# BATT_CPU_TEST_BED.net
KiCad netlist of a schematic drawn in EAGLE
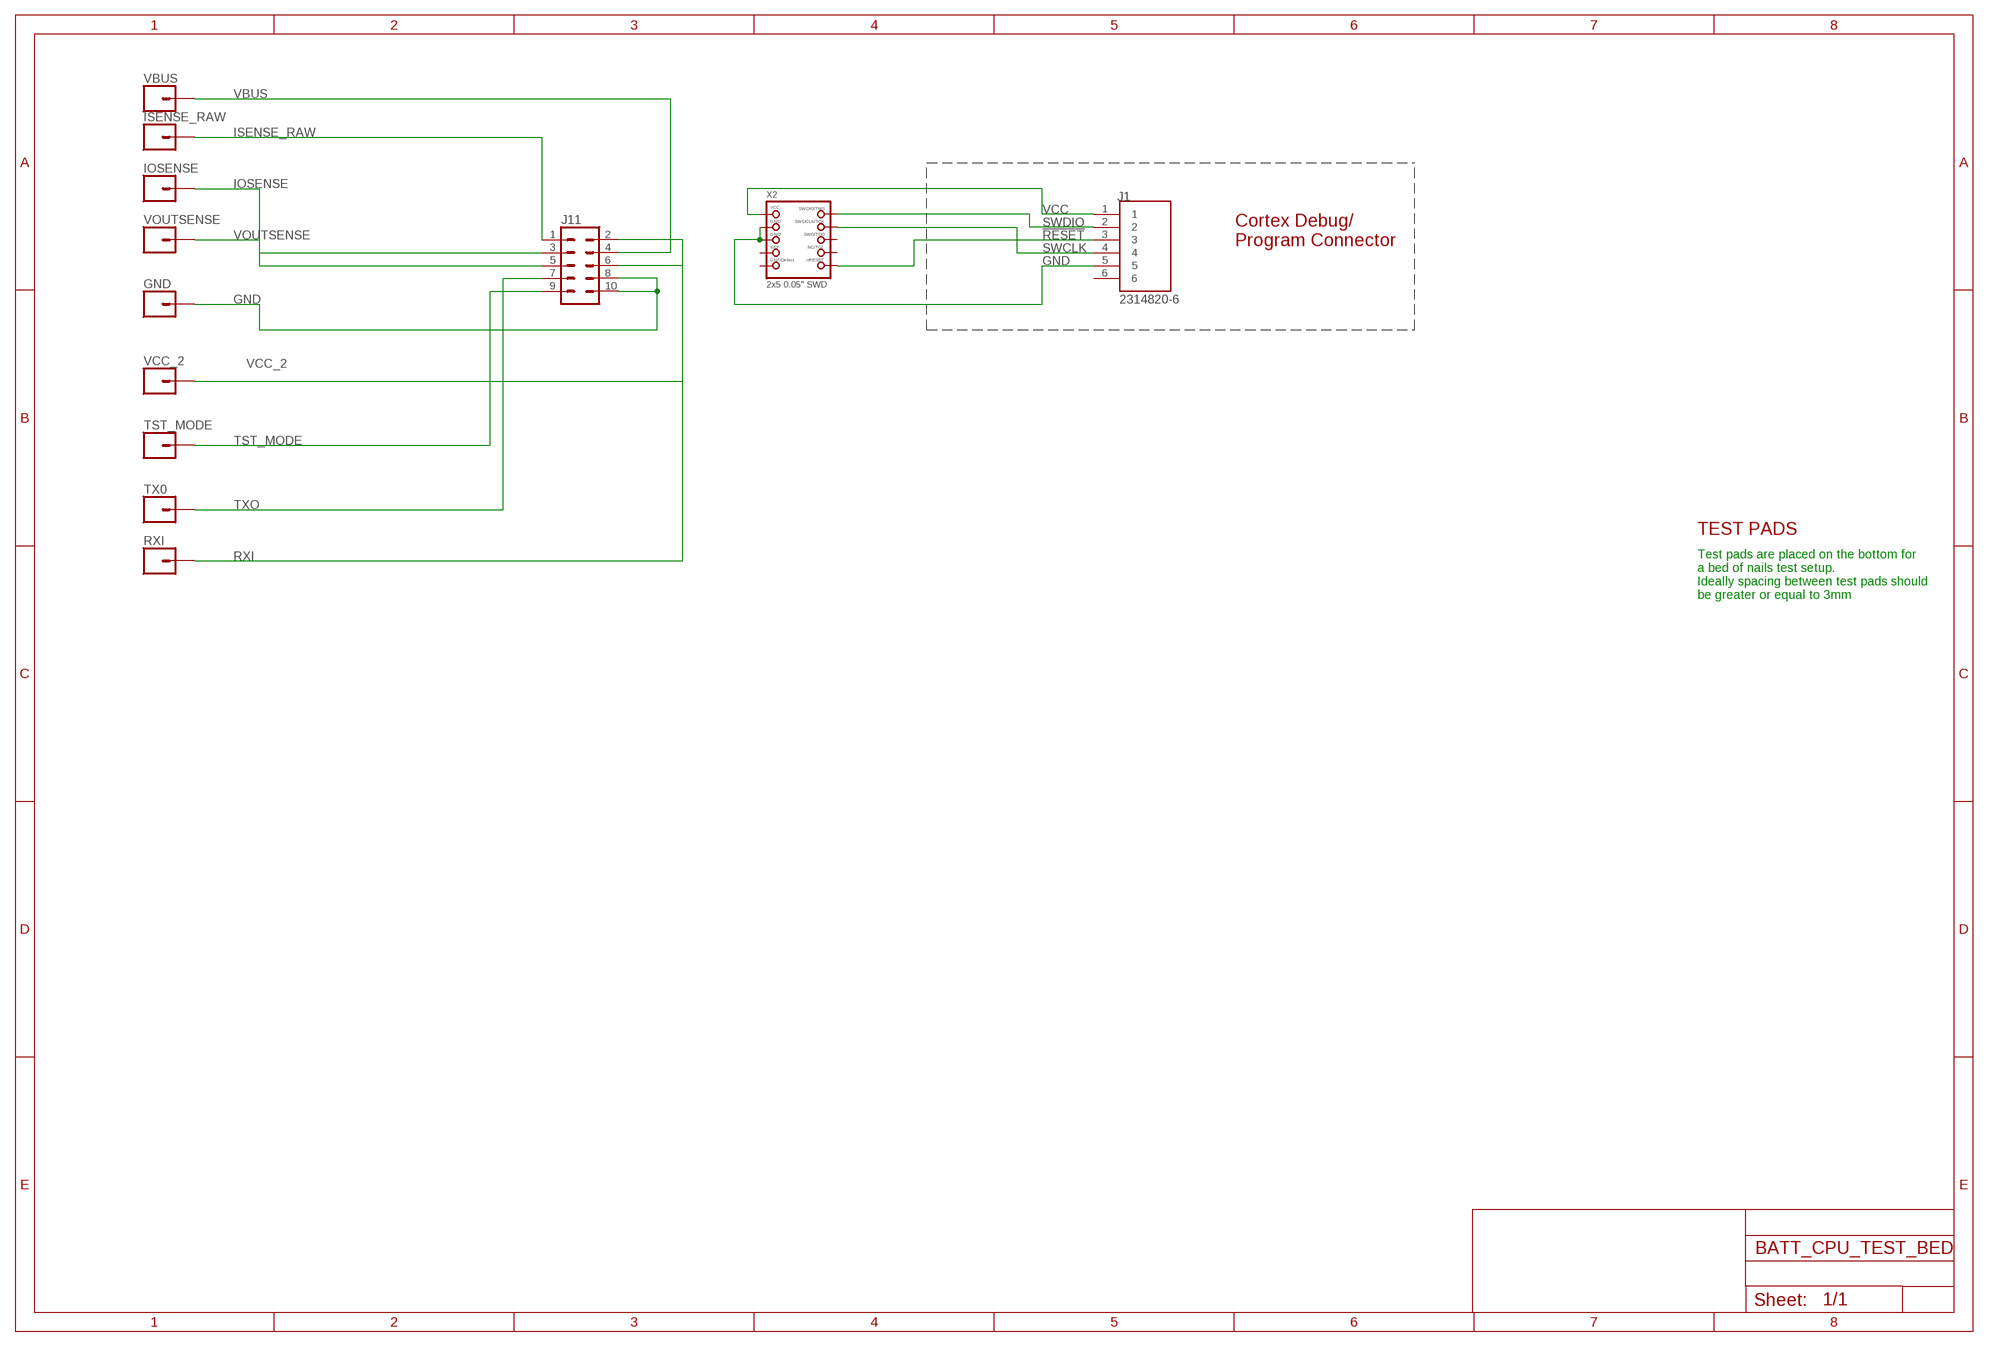
[diagram p0: schematic, sheet 1]

(export (version "E")
  (design (tool "Eeschema 10.0.6"))
  (components
    (comp (ref "GND")
      (value "CONN_01POGOPIN_HOLE_LARGE")
      (footprint "eagle-import:1X01_POGOPIN_HOLE_0.061_DIA")
      (libsource (lib "eagle-import") (part "CONN_01POGOPIN_HOLE_LARGE"))
    )
    (comp (ref "IOSENSE")
      (value "CONN_01POGOPIN_HOLE_LARGE")
      (footprint "eagle-import:1X01_POGOPIN_HOLE_0.061_DIA")
      (libsource (lib "eagle-import") (part "CONN_01POGOPIN_HOLE_LARGE"))
    )
    (comp (ref "ISENSE_RAW")
      (value "CONN_01POGOPIN_HOLE_LARGE")
      (footprint "eagle-import:1X01_POGOPIN_HOLE_0.061_DIA")
      (libsource (lib "eagle-import") (part "CONN_01POGOPIN_HOLE_LARGE"))
    )
    (comp (ref "J1")
      (value "2314820-6")
      (footprint "eagle-import:TE_2314820-6")
      (fields (field (name "DIGI-KEY_PART_NUMBER") "17-2314820-6-ND") (field (name "MF") "TE Connectivity"))
      (libsource (lib "eagle-import") (part "2314820-6"))
    )
    (comp (ref "J11")
      (value "CONN_05X2PTH")
      (footprint "eagle-import:2X5")
      (libsource (lib "eagle-import") (part "CONN_05X2PTH"))
    )
    (comp (ref "RXI")
      (value "CONN_01POGOPIN_HOLE_LARGE")
      (footprint "eagle-import:1X01_POGOPIN_HOLE_0.061_DIA")
      (libsource (lib "eagle-import") (part "CONN_01POGOPIN_HOLE_LARGE"))
    )
    (comp (ref "TST_MODE")
      (value "CONN_01POGOPIN_HOLE_LARGE")
      (footprint "eagle-import:1X01_POGOPIN_HOLE_0.061_DIA")
      (libsource (lib "eagle-import") (part "CONN_01POGOPIN_HOLE_LARGE"))
    )
    (comp (ref "TX0")
      (value "CONN_01POGOPIN_HOLE_LARGE")
      (footprint "eagle-import:1X01_POGOPIN_HOLE_0.061_DIA")
      (libsource (lib "eagle-import") (part "CONN_01POGOPIN_HOLE_LARGE"))
    )
    (comp (ref "VBUS")
      (value "CONN_01POGOPIN_HOLE_LARGE")
      (footprint "eagle-import:1X01_POGOPIN_HOLE_0.061_DIA")
      (libsource (lib "eagle-import") (part "CONN_01POGOPIN_HOLE_LARGE"))
    )
    (comp (ref "VCC_2")
      (value "CONN_01POGOPIN_HOLE_LARGE")
      (footprint "eagle-import:1X01_POGOPIN_HOLE_0.061_DIA")
      (libsource (lib "eagle-import") (part "CONN_01POGOPIN_HOLE_LARGE"))
    )
    (comp (ref "VOUTSENSE")
      (value "CONN_01POGOPIN_HOLE_LARGE")
      (footprint "eagle-import:1X01_POGOPIN_HOLE_0.061_DIA")
      (libsource (lib "eagle-import") (part "CONN_01POGOPIN_HOLE_LARGE"))
    )
    (comp (ref "X2")
      (value "2x5 0.05\" SWD")
      (footprint "eagle-import:2X05_1.27MM_BOX_POSTS")
      (libsource (lib "eagle-import") (part "JTAG-CORTEXBOXPOSTS"))
    )
  )
  (nets
    (net (code "1") (name "/GND") (class "Default")
      (node (ref "GND") (pin "2") (pinfunction "1_2") (pintype "passive"))
      (node (ref "J1") (pin "5") (pinfunction "5_5") (pintype "passive"))
      (node (ref "J11") (pin "10") (pinfunction "10_10") (pintype "passive"))
      (node (ref "J11") (pin "8") (pinfunction "8_8") (pintype "passive"))
      (node (ref "X2") (pin "3") (pinfunction "GND_3") (pintype "power_in"))
      (node (ref "X2") (pin "5") (pinfunction "GND_5") (pintype "power_in"))
    )
    (net (code "2") (name "/IOSENSE") (class "Default")
      (node (ref "IOSENSE") (pin "2") (pinfunction "1_2") (pintype "passive"))
      (node (ref "J11") (pin "3") (pinfunction "3_3") (pintype "passive"))
    )
    (net (code "3") (name "/ISENSE_RAW") (class "Default")
      (node (ref "ISENSE_RAW") (pin "2") (pinfunction "1_2") (pintype "passive"))
      (node (ref "J11") (pin "1") (pinfunction "1_1") (pintype "passive"))
    )
    (net (code "4") (name "/RXI") (class "Default")
      (node (ref "J11") (pin "6") (pinfunction "6_6") (pintype "passive"))
      (node (ref "RXI") (pin "2") (pinfunction "1_2") (pintype "passive"))
    )
    (net (code "5") (name "/SWCLK") (class "Default")
      (node (ref "J1") (pin "4") (pinfunction "4_4") (pintype "passive"))
      (node (ref "X2") (pin "4") (pinfunction "SWDCLK_4") (pintype "bidirectional"))
    )
    (net (code "6") (name "/SWDIO") (class "Default")
      (node (ref "J1") (pin "2") (pinfunction "2_2") (pintype "passive"))
      (node (ref "X2") (pin "2") (pinfunction "SWDIO_2") (pintype "bidirectional"))
    )
    (net (code "7") (name "/TST_MODE") (class "Default")
      (node (ref "J11") (pin "9") (pinfunction "9_9") (pintype "passive"))
      (node (ref "TST_MODE") (pin "2") (pinfunction "1_2") (pintype "passive"))
    )
    (net (code "8") (name "/TXO") (class "Default")
      (node (ref "J11") (pin "7") (pinfunction "7_7") (pintype "passive"))
      (node (ref "TX0") (pin "2") (pinfunction "1_2") (pintype "passive"))
    )
    (net (code "9") (name "/VBUS") (class "Default")
      (node (ref "J11") (pin "4") (pinfunction "4_4") (pintype "passive"))
      (node (ref "VBUS") (pin "2") (pinfunction "1_2") (pintype "passive"))
    )
    (net (code "10") (name "/VCC") (class "Default")
      (node (ref "J1") (pin "1") (pinfunction "1_1") (pintype "passive"))
      (node (ref "X2") (pin "1") (pinfunction "VCC_1") (pintype "power_in"))
    )
    (net (code "11") (name "/VCC_2") (class "Default")
      (node (ref "J11") (pin "2") (pinfunction "2_2") (pintype "passive"))
      (node (ref "VCC_2") (pin "2") (pinfunction "1_2") (pintype "passive"))
    )
    (net (code "12") (name "/VOUTSENSE") (class "Default")
      (node (ref "J11") (pin "5") (pinfunction "5_5") (pintype "passive"))
      (node (ref "VOUTSENSE") (pin "2") (pinfunction "1_2") (pintype "passive"))
    )
    (net (code "13") (name "/~{RESET}") (class "Default")
      (node (ref "J1") (pin "3") (pinfunction "3_3") (pintype "passive"))
      (node (ref "X2") (pin "10") (pinfunction "NRESET_10") (pintype "bidirectional"))
    )
    (net (code "14") (name "unconnected-(J1-Pad6)") (class "Default")
      (node (ref "J1") (pin "6") (pinfunction "6_6") (pintype "passive"))
    )
    (net (code "15") (name "unconnected-(X2-GNDDETECT-Pad9)") (class "Default")
      (node (ref "X2") (pin "9") (pinfunction "GNDDETECT_9") (pintype "bidirectional"))
    )
    (net (code "16") (name "unconnected-(X2-KEY-Pad7)") (class "Default")
      (node (ref "X2") (pin "7") (pinfunction "KEY_7") (pintype "bidirectional"))
    )
    (net (code "17") (name "unconnected-(X2-SWO-Pad6)") (class "Default")
      (node (ref "X2") (pin "6") (pinfunction "SWO_6") (pintype "bidirectional"))
    )
    (net (code "18") (name "unconnected-(X2-TDI-Pad8)") (class "Default")
      (node (ref "X2") (pin "8") (pinfunction "TDI_8") (pintype "bidirectional"))
    )
  )
)
